# 03cpu_sodimm.net
KiCad netlist of a schematic drawn in Altium Designer
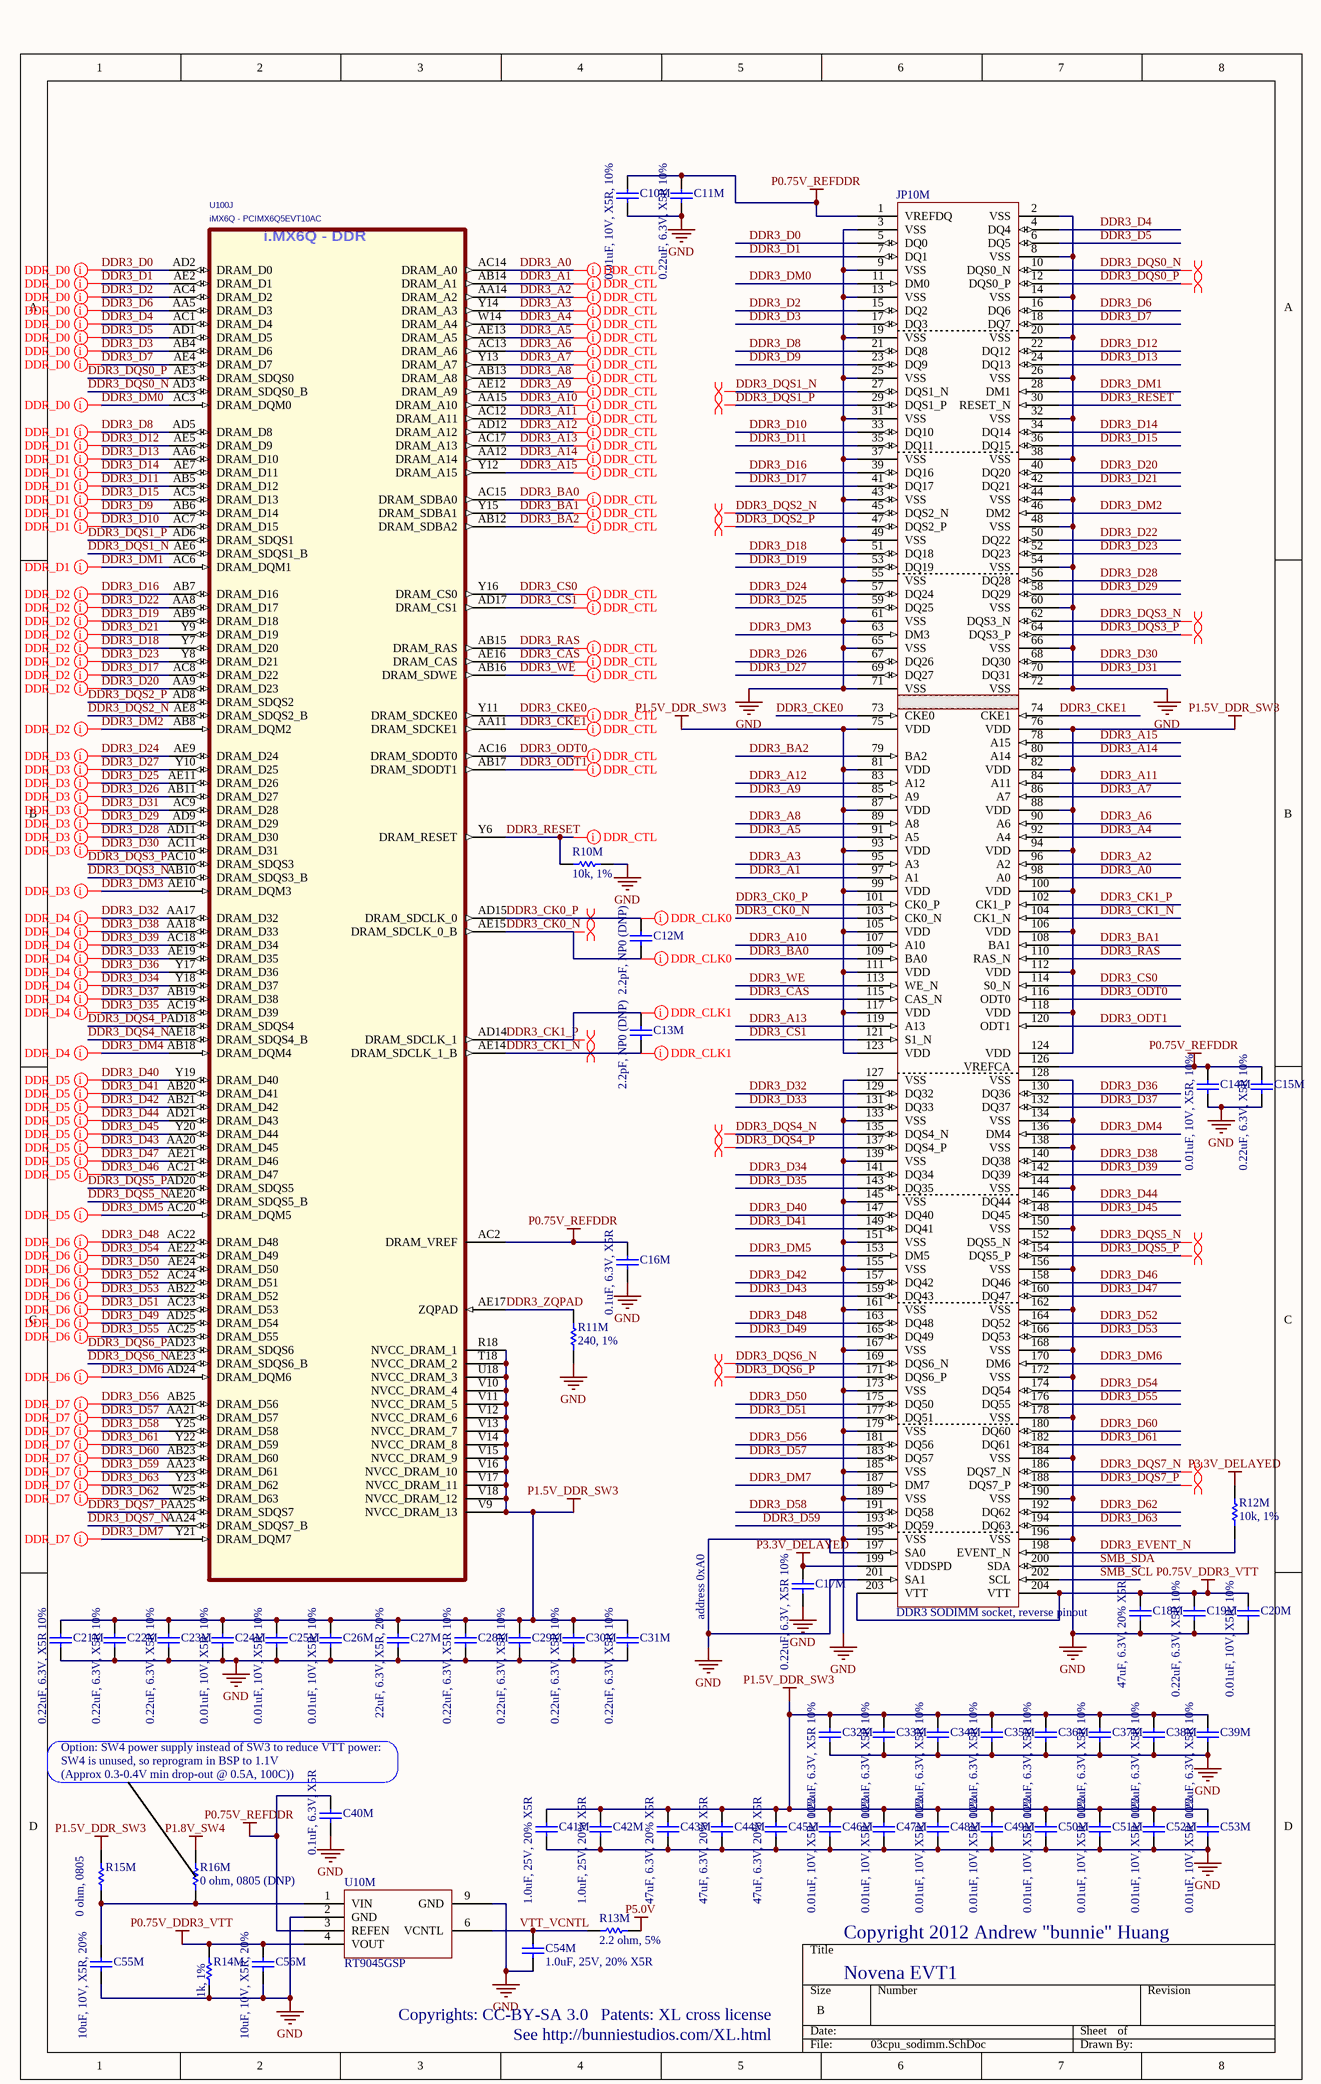
[diagram p0: 03cpu_sodimm.SchDoc]

(export (version "E")
  (design (tool "Eeschema 10.0.6"))
  (components
    (comp (ref "C10M")
      (value "0.01uF, 10V, X5R, 10%")
      (footprint "CAPC0603N_B")
      (description "Capacitor (Semiconductor SIM Model)")
      (fields (field (name "PUBLISHER") "Altium Limited"))
      (libsource (lib "Miscellaneous Devices") (part "Cap Semi"))
    )
    (comp (ref "C11M")
      (value "0.22uF, 6.3V, X5R 10%")
      (footprint "CAPC0603N_B")
      (description "CAP CER 0.22UF 6.3V 20% X5R 0201")
      (fields (field (name "PUBLISHER") "Altium Limited"))
      (libsource (lib "Miscellaneous Devices") (part "Cap Semi"))
    )
    (comp (ref "C12M")
      (value "2.2pF, NP0 (DNP)")
      (footprint "CAPC1005N")
      (description "Capacitor (Semiconductor SIM Model)")
      (fields (field (name "PUBLISHER") "Altium Limited"))
      (libsource (lib "Miscellaneous Devices") (part "Cap Semi"))
    )
    (comp (ref "C13M")
      (value "2.2pF, NP0 (DNP)")
      (footprint "CAPC1005N")
      (description "Capacitor (Semiconductor SIM Model)")
      (fields (field (name "PUBLISHER") "Altium Limited"))
      (libsource (lib "Miscellaneous Devices") (part "Cap Semi"))
    )
    (comp (ref "C14M")
      (value "0.01uF, 10V, X5R, 10%")
      (footprint "CAPC0603N_B")
      (description "Capacitor (Semiconductor SIM Model)")
      (fields (field (name "PUBLISHER") "Altium Limited"))
      (libsource (lib "Miscellaneous Devices") (part "Cap Semi"))
    )
    (comp (ref "C15M")
      (value "0.22uF, 6.3V, X5R 10%")
      (footprint "CAPC0603N_B")
      (description "CAP CER 0.22UF 6.3V 20% X5R 0201")
      (fields (field (name "PUBLISHER") "Altium Limited"))
      (libsource (lib "Miscellaneous Devices") (part "Cap Semi"))
    )
    (comp (ref "C16M")
      (value "0.1uF, 6.3V, X5R")
      (footprint "CAPC0603N_B")
      (description "Capacitor (Semiconductor SIM Model)")
      (fields (field (name "PUBLISHER") "Altium Limited"))
      (libsource (lib "Miscellaneous Devices") (part "Cap Semi"))
    )
    (comp (ref "C17M")
      (value "0.22uF, 6.3V, X5R 10%")
      (footprint "CAPC0603N_B")
      (description "CAP CER 0.22UF 6.3V 20% X5R 0201")
      (fields (field (name "PUBLISHER") "Altium Limited"))
      (libsource (lib "Miscellaneous Devices") (part "Cap Semi"))
    )
    (comp (ref "C18M")
      (value "47uF, 6.3V, 20% X5R")
      (footprint "CAPC3216N")
      (description "Capacitor (Semiconductor SIM Model)")
      (fields (field (name "PUBLISHER") "Altium Limited"))
      (libsource (lib "Miscellaneous Devices") (part "Cap Semi"))
    )
    (comp (ref "C19M")
      (value "0.22uF, 6.3V, X5R 10%")
      (footprint "CAPC0603N_B")
      (description "CAP CER 0.22UF 6.3V 20% X5R 0201")
      (fields (field (name "PUBLISHER") "Altium Limited"))
      (libsource (lib "Miscellaneous Devices") (part "Cap Semi"))
    )
    (comp (ref "C20M")
      (value "0.01uF, 10V, X5R, 10%")
      (footprint "CAPC0603N_B")
      (description "Capacitor (Semiconductor SIM Model)")
      (fields (field (name "PUBLISHER") "Altium Limited"))
      (libsource (lib "Miscellaneous Devices") (part "Cap Semi"))
    )
    (comp (ref "C21M")
      (value "0.22uF, 6.3V, X5R 10%")
      (footprint "CAPC0603N_B")
      (description "CAP CER 0.22UF 6.3V 20% X5R 0201")
      (fields (field (name "PUBLISHER") "Altium Limited"))
      (libsource (lib "Miscellaneous Devices") (part "Cap Semi"))
    )
    (comp (ref "C22M")
      (value "0.22uF, 6.3V, X5R 10%")
      (footprint "CAPC0603N_B")
      (description "CAP CER 0.22UF 6.3V 20% X5R 0201")
      (fields (field (name "PUBLISHER") "Altium Limited"))
      (libsource (lib "Miscellaneous Devices") (part "Cap Semi"))
    )
    (comp (ref "C23M")
      (value "0.22uF, 6.3V, X5R 10%")
      (footprint "CAPC0603N_B")
      (description "CAP CER 0.22UF 6.3V 20% X5R 0201")
      (fields (field (name "PUBLISHER") "Altium Limited"))
      (libsource (lib "Miscellaneous Devices") (part "Cap Semi"))
    )
    (comp (ref "C24M")
      (value "0.01uF, 10V, X5R, 10%")
      (footprint "CAPC0603N_B")
      (description "Capacitor (Semiconductor SIM Model)")
      (fields (field (name "PUBLISHER") "Altium Limited"))
      (libsource (lib "Miscellaneous Devices") (part "Cap Semi"))
    )
    (comp (ref "C25M")
      (value "0.01uF, 10V, X5R, 10%")
      (footprint "CAPC0603N_B")
      (description "Capacitor (Semiconductor SIM Model)")
      (fields (field (name "PUBLISHER") "Altium Limited"))
      (libsource (lib "Miscellaneous Devices") (part "Cap Semi"))
    )
    (comp (ref "C26M")
      (value "0.01uF, 10V, X5R, 10%")
      (footprint "CAPC0603N_B")
      (description "Capacitor (Semiconductor SIM Model)")
      (fields (field (name "PUBLISHER") "Altium Limited"))
      (libsource (lib "Miscellaneous Devices") (part "Cap Semi"))
    )
    (comp (ref "C27M")
      (value "22uF, 6.3V, X5R, 20%")
      (footprint "CAPC1608N_HD")
      (description "Capacitor (Semiconductor SIM Model)")
      (fields (field (name "PUBLISHER") "Altium Limited"))
      (libsource (lib "Miscellaneous Devices") (part "Cap Semi"))
    )
    (comp (ref "C28M")
      (value "0.22uF, 6.3V, X5R 10%")
      (footprint "CAPC0603N_B")
      (description "CAP CER 0.22UF 6.3V 20% X5R 0201")
      (fields (field (name "PUBLISHER") "Altium Limited"))
      (libsource (lib "Miscellaneous Devices") (part "Cap Semi"))
    )
    (comp (ref "C29M")
      (value "0.22uF, 6.3V, X5R 10%")
      (footprint "CAPC0603N_B")
      (description "CAP CER 0.22UF 6.3V 20% X5R 0201")
      (fields (field (name "PUBLISHER") "Altium Limited"))
      (libsource (lib "Miscellaneous Devices") (part "Cap Semi"))
    )
    (comp (ref "C30M")
      (value "0.22uF, 6.3V, X5R 10%")
      (footprint "CAPC0603N_B")
      (description "CAP CER 0.22UF 6.3V 20% X5R 0201")
      (fields (field (name "PUBLISHER") "Altium Limited"))
      (libsource (lib "Miscellaneous Devices") (part "Cap Semi"))
    )
    (comp (ref "C31M")
      (value "0.22uF, 6.3V, X5R 10%")
      (footprint "CAPC0603N_B")
      (description "CAP CER 0.22UF 6.3V 20% X5R 0201")
      (fields (field (name "PUBLISHER") "Altium Limited"))
      (libsource (lib "Miscellaneous Devices") (part "Cap Semi"))
    )
    (comp (ref "C32M")
      (value "0.22uF, 6.3V, X5R 10%")
      (footprint "CAPC0603N_B")
      (description "CAP CER 0.22UF 6.3V 20% X5R 0201")
      (fields (field (name "PUBLISHER") "Altium Limited"))
      (libsource (lib "Miscellaneous Devices") (part "Cap Semi"))
    )
    (comp (ref "C33M")
      (value "0.22uF, 6.3V, X5R 10%")
      (footprint "CAPC0603N_B")
      (description "CAP CER 0.22UF 6.3V 20% X5R 0201")
      (fields (field (name "PUBLISHER") "Altium Limited"))
      (libsource (lib "Miscellaneous Devices") (part "Cap Semi"))
    )
    (comp (ref "C34M")
      (value "0.22uF, 6.3V, X5R 10%")
      (footprint "CAPC0603N_B")
      (description "CAP CER 0.22UF 6.3V 20% X5R 0201")
      (fields (field (name "PUBLISHER") "Altium Limited"))
      (libsource (lib "Miscellaneous Devices") (part "Cap Semi"))
    )
    (comp (ref "C35M")
      (value "0.22uF, 6.3V, X5R 10%")
      (footprint "CAPC0603N_B")
      (description "CAP CER 0.22UF 6.3V 20% X5R 0201")
      (fields (field (name "PUBLISHER") "Altium Limited"))
      (libsource (lib "Miscellaneous Devices") (part "Cap Semi"))
    )
    (comp (ref "C36M")
      (value "0.22uF, 6.3V, X5R 10%")
      (footprint "CAPC0603N_B")
      (description "CAP CER 0.22UF 6.3V 20% X5R 0201")
      (fields (field (name "PUBLISHER") "Altium Limited"))
      (libsource (lib "Miscellaneous Devices") (part "Cap Semi"))
    )
    (comp (ref "C37M")
      (value "0.22uF, 6.3V, X5R 10%")
      (footprint "CAPC0603N_B")
      (description "CAP CER 0.22UF 6.3V 20% X5R 0201")
      (fields (field (name "PUBLISHER") "Altium Limited"))
      (libsource (lib "Miscellaneous Devices") (part "Cap Semi"))
    )
    (comp (ref "C38M")
      (value "0.22uF, 6.3V, X5R 10%")
      (footprint "CAPC0603N_B")
      (description "CAP CER 0.22UF 6.3V 20% X5R 0201")
      (fields (field (name "PUBLISHER") "Altium Limited"))
      (libsource (lib "Miscellaneous Devices") (part "Cap Semi"))
    )
    (comp (ref "C39M")
      (value "0.22uF, 6.3V, X5R 10%")
      (footprint "CAPC0603N_B")
      (description "CAP CER 0.22UF 6.3V 20% X5R 0201")
      (fields (field (name "PUBLISHER") "Altium Limited"))
      (libsource (lib "Miscellaneous Devices") (part "Cap Semi"))
    )
    (comp (ref "C40M")
      (value "0.1uF, 6.3V, X5R")
      (footprint "CAPC0603N_B")
      (description "Capacitor (Semiconductor SIM Model)")
      (fields (field (name "PUBLISHER") "Altium Limited"))
      (libsource (lib "Miscellaneous Devices") (part "Cap Semi"))
    )
    (comp (ref "C41M")
      (value "1.0uF, 25V, 20% X5R")
      (footprint "CAPC1608N")
      (description "Capacitor (Semiconductor SIM Model)")
      (fields (field (name "PUBLISHER") "Altium Limited"))
      (libsource (lib "Miscellaneous Devices") (part "Cap Semi"))
    )
    (comp (ref "C42M")
      (value "1.0uF, 25V, 20% X5R")
      (footprint "CAPC1608N")
      (description "Capacitor (Semiconductor SIM Model)")
      (fields (field (name "PUBLISHER") "Altium Limited"))
      (libsource (lib "Miscellaneous Devices") (part "Cap Semi"))
    )
    (comp (ref "C43M")
      (value "47uF, 6.3V, 20% X5R")
      (footprint "CAPC3216N")
      (description "Capacitor (Semiconductor SIM Model)")
      (fields (field (name "PUBLISHER") "Altium Limited"))
      (libsource (lib "Miscellaneous Devices") (part "Cap Semi"))
    )
    (comp (ref "C44M")
      (value "47uF, 6.3V, 20% X5R")
      (footprint "CAPC3216N")
      (description "Capacitor (Semiconductor SIM Model)")
      (fields (field (name "PUBLISHER") "Altium Limited"))
      (libsource (lib "Miscellaneous Devices") (part "Cap Semi"))
    )
    (comp (ref "C45M")
      (value "47uF, 6.3V, 20% X5R")
      (footprint "CAPC3216N")
      (description "Capacitor (Semiconductor SIM Model)")
      (fields (field (name "PUBLISHER") "Altium Limited"))
      (libsource (lib "Miscellaneous Devices") (part "Cap Semi"))
    )
    (comp (ref "C46M")
      (value "0.01uF, 10V, X5R, 10%")
      (footprint "CAPC0603N_B")
      (description "Capacitor (Semiconductor SIM Model)")
      (fields (field (name "PUBLISHER") "Altium Limited"))
      (libsource (lib "Miscellaneous Devices") (part "Cap Semi"))
    )
    (comp (ref "C47M")
      (value "0.01uF, 10V, X5R, 10%")
      (footprint "CAPC0603N_B")
      (description "Capacitor (Semiconductor SIM Model)")
      (fields (field (name "PUBLISHER") "Altium Limited"))
      (libsource (lib "Miscellaneous Devices") (part "Cap Semi"))
    )
    (comp (ref "C48M")
      (value "0.01uF, 10V, X5R, 10%")
      (footprint "CAPC0603N_B")
      (description "Capacitor (Semiconductor SIM Model)")
      (fields (field (name "PUBLISHER") "Altium Limited"))
      (libsource (lib "Miscellaneous Devices") (part "Cap Semi"))
    )
    (comp (ref "C49M")
      (value "0.01uF, 10V, X5R, 10%")
      (footprint "CAPC0603N_B")
      (description "Capacitor (Semiconductor SIM Model)")
      (fields (field (name "PUBLISHER") "Altium Limited"))
      (libsource (lib "Miscellaneous Devices") (part "Cap Semi"))
    )
    (comp (ref "C50M")
      (value "0.01uF, 10V, X5R, 10%")
      (footprint "CAPC0603N_B")
      (description "Capacitor (Semiconductor SIM Model)")
      (fields (field (name "PUBLISHER") "Altium Limited"))
      (libsource (lib "Miscellaneous Devices") (part "Cap Semi"))
    )
    (comp (ref "C51M")
      (value "0.01uF, 10V, X5R, 10%")
      (footprint "CAPC0603N_B")
      (description "Capacitor (Semiconductor SIM Model)")
      (fields (field (name "PUBLISHER") "Altium Limited"))
      (libsource (lib "Miscellaneous Devices") (part "Cap Semi"))
    )
    (comp (ref "C52M")
      (value "0.01uF, 10V, X5R, 10%")
      (footprint "CAPC0603N_B")
      (description "Capacitor (Semiconductor SIM Model)")
      (fields (field (name "PUBLISHER") "Altium Limited"))
      (libsource (lib "Miscellaneous Devices") (part "Cap Semi"))
    )
    (comp (ref "C53M")
      (value "0.01uF, 10V, X5R, 10%")
      (footprint "CAPC0603N_B")
      (description "Capacitor (Semiconductor SIM Model)")
      (fields (field (name "PUBLISHER") "Altium Limited"))
      (libsource (lib "Miscellaneous Devices") (part "Cap Semi"))
    )
    (comp (ref "C54M")
      (value "1.0uF, 25V, 20% X5R")
      (footprint "CAPC1608N")
      (description "Capacitor (Semiconductor SIM Model)")
      (fields (field (name "PUBLISHER") "Altium Limited"))
      (libsource (lib "Miscellaneous Devices") (part "Cap Semi"))
    )
    (comp (ref "C55M")
      (value "10uF, 10V, X5R, 20%")
      (footprint "CAPC1608N")
      (description "Capacitor (Semiconductor SIM Model)")
      (fields (field (name "PUBLISHER") "Altium Limited"))
      (libsource (lib "Miscellaneous Devices") (part "Cap Semi"))
    )
    (comp (ref "C56M")
      (value "10uF, 10V, X5R, 20%")
      (footprint "CAPC1608N")
      (description "Capacitor (Semiconductor SIM Model)")
      (fields (field (name "PUBLISHER") "Altium Limited"))
      (libsource (lib "Miscellaneous Devices") (part "Cap Semi"))
    )
    (comp (ref "JP10M")
      (value "DDR3 SODIMM socket, reverse pinout")
      (footprint "DDR3_SODIMM_REV")
      (description "TE Connectivity 2013311 or equiv (9.2mm height)")
      (libsource (lib "commonsch") (part "DDR3_SODIMM"))
    )
    (comp (ref "R10M")
      (value "10k, 1%")
      (footprint "RESC1005N")
      (description "Resistor")
      (fields (field (name "PUBLISHER") "Altium Limited"))
      (libsource (lib "Miscellaneous Devices") (part "Res1"))
    )
    (comp (ref "R11M")
      (value "240, 1%")
      (footprint "RESC1005N")
      (description "Resistor")
      (fields (field (name "PUBLISHER") "Altium Limited"))
      (libsource (lib "Miscellaneous Devices") (part "Res1"))
    )
    (comp (ref "R12M")
      (value "10k, 1%")
      (footprint "RESC1005N")
      (description "Resistor")
      (fields (field (name "PUBLISHER") "Altium Limited"))
      (libsource (lib "Miscellaneous Devices") (part "Res1"))
    )
    (comp (ref "R13M")
      (value "2.2 ohm, 5%")
      (footprint "RESC1005N")
      (description "Resistor")
      (fields (field (name "PUBLISHER") "Altium Limited"))
      (libsource (lib "Miscellaneous Devices") (part "Res1"))
    )
    (comp (ref "R14M")
      (value "1k, 1%")
      (footprint "RESC1005N")
      (description "Resistor")
      (fields (field (name "PUBLISHER") "Altium Limited"))
      (libsource (lib "Miscellaneous Devices") (part "Res1"))
    )
    (comp (ref "R15M")
      (value "0 ohm, 0805")
      (footprint "RESC2012N")
      (description "Resistor")
      (fields (field (name "PUBLISHER") "Altium Limited"))
      (libsource (lib "Miscellaneous Devices") (part "Res1"))
    )
    (comp (ref "R16M")
      (value "0 ohm, 0805 (DNP)")
      (footprint "RESC2012N")
      (description "Resistor")
      (fields (field (name "PUBLISHER") "Altium Limited"))
      (libsource (lib "Miscellaneous Devices") (part "Res1"))
    )
    (comp (ref "U10M")
      (value "RT9045GSP")
      (footprint "SOIC127P600_HS-8N")
      (description "1.8A sink/source bus termination regulator (VTT)")
      (libsource (lib "commonsch") (part "RT9045GSP"))
    )
    (comp (ref "U100")
      (value "iMX6Q - PCIMX6Q5EVT10AC")
      (description "PLACEHOLDER FOR FREESCALE PART NUMBER PMCIMX6Q6VV1A.")
      (libsource (lib "*") (part "PCIMX6Q6VV1A"))
    )
  )
  (nets
    (net (code "1") (name "/DDR3_A0") (class "Default")
      (node (ref "JP10M") (pin "98") (pinfunction "A0_98") (pintype "input"))
      (node (ref "U100") (pin "AC14") (pinfunction "DRAM_A0_AC14") (pintype "output"))
    )
    (net (code "2") (name "/DDR3_A1") (class "Default")
      (node (ref "JP10M") (pin "97") (pinfunction "A1_97") (pintype "input"))
      (node (ref "U100") (pin "AB14") (pinfunction "DRAM_A1_AB14") (pintype "output"))
    )
    (net (code "3") (name "/DDR3_A2") (class "Default")
      (node (ref "JP10M") (pin "96") (pinfunction "A2_96") (pintype "input"))
      (node (ref "U100") (pin "AA14") (pinfunction "DRAM_A2_AA14") (pintype "output"))
    )
    (net (code "4") (name "/DDR3_A3") (class "Default")
      (node (ref "JP10M") (pin "95") (pinfunction "A3_95") (pintype "input"))
      (node (ref "U100") (pin "Y14") (pinfunction "DRAM_A3_Y14") (pintype "output"))
    )
    (net (code "5") (name "/DDR3_A4") (class "Default")
      (node (ref "JP10M") (pin "92") (pinfunction "A4_92") (pintype "input"))
      (node (ref "U100") (pin "W14") (pinfunction "DRAM_A4_W14") (pintype "output"))
    )
    (net (code "6") (name "/DDR3_A5") (class "Default")
      (node (ref "JP10M") (pin "91") (pinfunction "A5_91") (pintype "input"))
      (node (ref "U100") (pin "AE13") (pinfunction "DRAM_A5_AE13") (pintype "output"))
    )
    (net (code "7") (name "/DDR3_A6") (class "Default")
      (node (ref "JP10M") (pin "90") (pinfunction "A6_90") (pintype "input"))
      (node (ref "U100") (pin "AC13") (pinfunction "DRAM_A6_AC13") (pintype "output"))
    )
    (net (code "8") (name "/DDR3_A7") (class "Default")
      (node (ref "JP10M") (pin "86") (pinfunction "A7_86") (pintype "input"))
      (node (ref "U100") (pin "Y13") (pinfunction "DRAM_A7_Y13") (pintype "output"))
    )
    (net (code "9") (name "/DDR3_A8") (class "Default")
      (node (ref "JP10M") (pin "89") (pinfunction "A8_89") (pintype "input"))
      (node (ref "U100") (pin "AB13") (pinfunction "DRAM_A8_AB13") (pintype "output"))
    )
    (net (code "10") (name "/DDR3_A9") (class "Default")
      (node (ref "JP10M") (pin "85") (pinfunction "A9_85") (pintype "input"))
      (node (ref "U100") (pin "AE12") (pinfunction "DRAM_A9_AE12") (pintype "output"))
    )
    (net (code "11") (name "/DDR3_A10") (class "Default")
      (node (ref "JP10M") (pin "107") (pinfunction "A10_107") (pintype "input"))
      (node (ref "U100") (pin "AA15") (pinfunction "DRAM_A10_AA15") (pintype "output"))
    )
    (net (code "12") (name "/DDR3_A11") (class "Default")
      (node (ref "JP10M") (pin "84") (pinfunction "A11_84") (pintype "input"))
      (node (ref "U100") (pin "AC12") (pinfunction "DRAM_A11_AC12") (pintype "output"))
    )
    (net (code "13") (name "/DDR3_A12") (class "Default")
      (node (ref "JP10M") (pin "83") (pinfunction "A12_83") (pintype "input"))
      (node (ref "U100") (pin "AD12") (pinfunction "DRAM_A12_AD12") (pintype "output"))
    )
    (net (code "14") (name "/DDR3_A13") (class "Default")
      (node (ref "JP10M") (pin "119") (pinfunction "A13_119") (pintype "input"))
      (node (ref "U100") (pin "AC17") (pinfunction "DRAM_A13_AC17") (pintype "output"))
    )
    (net (code "15") (name "/DDR3_A14") (class "Default")
      (node (ref "JP10M") (pin "80") (pinfunction "A14_80") (pintype "input"))
      (node (ref "U100") (pin "AA12") (pinfunction "DRAM_A14_AA12") (pintype "output"))
    )
    (net (code "16") (name "/DDR3_A15") (class "Default")
      (node (ref "JP10M") (pin "78") (pinfunction "A15_78") (pintype "input"))
      (node (ref "U100") (pin "Y12") (pinfunction "DRAM_A15_Y12") (pintype "output"))
    )
    (net (code "17") (name "/DDR3_BA0") (class "Default")
      (node (ref "JP10M") (pin "109") (pinfunction "BA0_109") (pintype "input"))
      (node (ref "U100") (pin "AC15") (pinfunction "DRAM_SDBA0_AC15") (pintype "output"))
    )
    (net (code "18") (name "/DDR3_BA1") (class "Default")
      (node (ref "JP10M") (pin "108") (pinfunction "BA1_108") (pintype "input"))
      (node (ref "U100") (pin "Y15") (pinfunction "DRAM_SDBA1_Y15") (pintype "output"))
    )
    (net (code "19") (name "/DDR3_BA2") (class "Default")
      (node (ref "JP10M") (pin "79") (pinfunction "BA2_79") (pintype "input"))
      (node (ref "U100") (pin "AB12") (pinfunction "DRAM_SDBA2_AB12") (pintype "output"))
    )
    (net (code "20") (name "/DDR3_CAS") (class "Default")
      (node (ref "JP10M") (pin "115") (pinfunction "CAS_N_115") (pintype "input"))
      (node (ref "U100") (pin "AE16") (pinfunction "DRAM_CAS_AE16") (pintype "output"))
    )
    (net (code "21") (name "/DDR3_CK0_N") (class "Default")
      (node (ref "C12M") (pin "2") (pinfunction "2_2") (pintype "passive"))
      (node (ref "JP10M") (pin "103") (pinfunction "CK0_N_103") (pintype "input"))
      (node (ref "U100") (pin "AE15") (pinfunction "DRAM_SDCLK_0_B_AE15") (pintype "output"))
    )
    (net (code "22") (name "/DDR3_CK0_P") (class "Default")
      (node (ref "C12M") (pin "1") (pinfunction "1_1") (pintype "passive"))
      (node (ref "JP10M") (pin "101") (pinfunction "CK0_P_101") (pintype "input"))
      (node (ref "U100") (pin "AD15") (pinfunction "DRAM_SDCLK_0_AD15") (pintype "output"))
    )
    (net (code "23") (name "/DDR3_CK1_N") (class "Default")
      (node (ref "C13M") (pin "2") (pinfunction "2_2") (pintype "passive"))
      (node (ref "JP10M") (pin "104") (pinfunction "CK1_N_104") (pintype "input"))
      (node (ref "U100") (pin "AE14") (pinfunction "DRAM_SDCLK_1_B_AE14") (pintype "output"))
    )
    (net (code "24") (name "/DDR3_CK1_P") (class "Default")
      (node (ref "C13M") (pin "1") (pinfunction "1_1") (pintype "passive"))
      (node (ref "JP10M") (pin "102") (pinfunction "CK1_P_102") (pintype "input"))
      (node (ref "U100") (pin "AD14") (pinfunction "DRAM_SDCLK_1_AD14") (pintype "output"))
    )
    (net (code "25") (name "/DDR3_CKE0") (class "Default")
      (node (ref "JP10M") (pin "73") (pinfunction "CKE0_73") (pintype "input"))
      (node (ref "U100") (pin "Y11") (pinfunction "DRAM_SDCKE0_Y11") (pintype "output"))
    )
    (net (code "26") (name "/DDR3_CKE1") (class "Default")
      (node (ref "JP10M") (pin "74") (pinfunction "CKE1_74") (pintype "input"))
      (node (ref "U100") (pin "AA11") (pinfunction "DRAM_SDCKE1_AA11") (pintype "output"))
    )
    (net (code "27") (name "/DDR3_CS0") (class "Default")
      (node (ref "JP10M") (pin "114") (pinfunction "S0_N_114") (pintype "input"))
      (node (ref "U100") (pin "Y16") (pinfunction "DRAM_CS0_Y16") (pintype "output"))
    )
    (net (code "28") (name "/DDR3_CS1") (class "Default")
      (node (ref "JP10M") (pin "121") (pinfunction "S1_N_121") (pintype "input"))
      (node (ref "U100") (pin "AD17") (pinfunction "DRAM_CS1_AD17") (pintype "output"))
    )
    (net (code "29") (name "/DDR3_D0") (class "Default")
      (node (ref "JP10M") (pin "5") (pinfunction "DQ0_5") (pintype "bidirectional"))
      (node (ref "U100") (pin "AD2") (pinfunction "DRAM_D0_AD2") (pintype "bidirectional"))
    )
    (net (code "30") (name "/DDR3_D1") (class "Default")
      (node (ref "JP10M") (pin "7") (pinfunction "DQ1_7") (pintype "bidirectional"))
      (node (ref "U100") (pin "AE2") (pinfunction "DRAM_D1_AE2") (pintype "bidirectional"))
    )
    (net (code "31") (name "/DDR3_D2") (class "Default")
      (node (ref "JP10M") (pin "15") (pinfunction "DQ2_15") (pintype "bidirectional"))
      (node (ref "U100") (pin "AC4") (pinfunction "DRAM_D2_AC4") (pintype "bidirectional"))
    )
    (net (code "32") (name "/DDR3_D3") (class "Default")
      (node (ref "JP10M") (pin "17") (pinfunction "DQ3_17") (pintype "bidirectional"))
      (node (ref "U100") (pin "AB4") (pinfunction "DRAM_D6_AB4") (pintype "bidirectional"))
    )
    (net (code "33") (name "/DDR3_D4") (class "Default")
      (node (ref "JP10M") (pin "4") (pinfunction "DQ4_4") (pintype "bidirectional"))
      (node (ref "U100") (pin "AC1") (pinfunction "DRAM_D4_AC1") (pintype "bidirectional"))
    )
    (net (code "34") (name "/DDR3_D5") (class "Default")
      (node (ref "JP10M") (pin "6") (pinfunction "DQ5_6") (pintype "bidirectional"))
      (node (ref "U100") (pin "AD1") (pinfunction "DRAM_D5_AD1") (pintype "bidirectional"))
    )
    (net (code "35") (name "/DDR3_D6") (class "Default")
      (node (ref "JP10M") (pin "16") (pinfunction "DQ6_16") (pintype "bidirectional"))
      (node (ref "U100") (pin "AA5") (pinfunction "DRAM_D3_AA5") (pintype "bidirectional"))
    )
    (net (code "36") (name "/DDR3_D7") (class "Default")
      (node (ref "JP10M") (pin "18") (pinfunction "DQ7_18") (pintype "bidirectional"))
      (node (ref "U100") (pin "AE4") (pinfunction "DRAM_D7_AE4") (pintype "bidirectional"))
    )
    (net (code "37") (name "/DDR3_D8") (class "Default")
      (node (ref "JP10M") (pin "21") (pinfunction "DQ8_21") (pintype "bidirectional"))
      (node (ref "U100") (pin "AD5") (pinfunction "DRAM_D8_AD5") (pintype "bidirectional"))
    )
    (net (code "38") (name "/DDR3_D9") (class "Default")
      (node (ref "JP10M") (pin "23") (pinfunction "DQ9_23") (pintype "bidirectional"))
      (node (ref "U100") (pin "AB6") (pinfunction "DRAM_D14_AB6") (pintype "bidirectional"))
    )
    (net (code "39") (name "/DDR3_D10") (class "Default")
      (node (ref "JP10M") (pin "33") (pinfunction "DQ10_33") (pintype "bidirectional"))
      (node (ref "U100") (pin "AC7") (pinfunction "DRAM_D15_AC7") (pintype "bidirectional"))
    )
    (net (code "40") (name "/DDR3_D11") (class "Default")
      (node (ref "JP10M") (pin "35") (pinfunction "DQ11_35") (pintype "bidirectional"))
      (node (ref "U100") (pin "AB5") (pinfunction "DRAM_D12_AB5") (pintype "bidirectional"))
    )
    (net (code "41") (name "/DDR3_D12") (class "Default")
      (node (ref "JP10M") (pin "22") (pinfunction "DQ12_22") (pintype "bidirectional"))
      (node (ref "U100") (pin "AE5") (pinfunction "DRAM_D9_AE5") (pintype "bidirectional"))
    )
    (net (code "42") (name "/DDR3_D13") (class "Default")
      (node (ref "JP10M") (pin "24") (pinfunction "DQ13_24") (pintype "bidirectional"))
      (node (ref "U100") (pin "AA6") (pinfunction "DRAM_D10_AA6") (pintype "bidirectional"))
    )
    (net (code "43") (name "/DDR3_D14") (class "Default")
      (node (ref "JP10M") (pin "34") (pinfunction "DQ14_34") (pintype "bidirectional"))
      (node (ref "U100") (pin "AE7") (pinfunction "DRAM_D11_AE7") (pintype "bidirectional"))
    )
    (net (code "44") (name "/DDR3_D15") (class "Default")
      (node (ref "JP10M") (pin "36") (pinfunction "DQ15_36") (pintype "bidirectional"))
      (node (ref "U100") (pin "AC5") (pinfunction "DRAM_D13_AC5") (pintype "bidirectional"))
    )
    (net (code "45") (name "/DDR3_D16") (class "Default")
      (node (ref "JP10M") (pin "39") (pinfunction "DQ16_39") (pintype "bidirectional"))
      (node (ref "U100") (pin "AB7") (pinfunction "DRAM_D16_AB7") (pintype "bidirectional"))
    )
    (net (code "46") (name "/DDR3_D17") (class "Default")
      (node (ref "JP10M") (pin "41") (pinfunction "DQ17_41") (pintype "bidirectional"))
      (node (ref "U100") (pin "AC8") (pinfunction "DRAM_D22_AC8") (pintype "bidirectional"))
    )
    (net (code "47") (name "/DDR3_D18") (class "Default")
      (node (ref "JP10M") (pin "51") (pinfunction "DQ18_51") (pintype "bidirectional"))
      (node (ref "U100") (pin "Y7") (pinfunction "DRAM_D20_Y7") (pintype "bidirectional"))
    )
    (net (code "48") (name "/DDR3_D19") (class "Default")
      (node (ref "JP10M") (pin "53") (pinfunction "DQ19_53") (pintype "bidirectional"))
      (node (ref "U100") (pin "AB9") (pinfunction "DRAM_D18_AB9") (pintype "bidirectional"))
    )
    (net (code "49") (name "/DDR3_D20") (class "Default")
      (node (ref "JP10M") (pin "40") (pinfunction "DQ20_40") (pintype "bidirectional"))
      (node (ref "U100") (pin "AA9") (pinfunction "DRAM_D23_AA9") (pintype "bidirectional"))
    )
    (net (code "50") (name "/DDR3_D21") (class "Default")
      (node (ref "JP10M") (pin "42") (pinfunction "DQ21_42") (pintype "bidirectional"))
      (node (ref "U100") (pin "Y9") (pinfunction "DRAM_D19_Y9") (pintype "bidirectional"))
    )
    (net (code "51") (name "/DDR3_D22") (class "Default")
      (node (ref "JP10M") (pin "50") (pinfunction "DQ22_50") (pintype "bidirectional"))
      (node (ref "U100") (pin "AA8") (pinfunction "DRAM_D17_AA8") (pintype "bidirectional"))
    )
    (net (code "52") (name "/DDR3_D23") (class "Default")
      (node (ref "JP10M") (pin "52") (pinfunction "DQ23_52") (pintype "bidirectional"))
      (node (ref "U100") (pin "Y8") (pinfunction "DRAM_D21_Y8") (pintype "bidirectional"))
    )
    (net (code "53") (name "/DDR3_D24") (class "Default")
      (node (ref "JP10M") (pin "57") (pinfunction "DQ24_57") (pintype "bidirectional"))
      (node (ref "U100") (pin "AE9") (pinfunction "DRAM_D24_AE9") (pintype "bidirectional"))
    )
    (net (code "54") (name "/DDR3_D25") (class "Default")
      (node (ref "JP10M") (pin "59") (pinfunction "DQ25_59") (pintype "bidirectional"))
      (node (ref "U100") (pin "AE11") (pinfunction "DRAM_D26_AE11") (pintype "bidirectional"))
    )
    (net (code "55") (name "/DDR3_D26") (class "Default")
      (node (ref "JP10M") (pin "67") (pinfunction "DQ26_67") (pintype "bidirectional"))
      (node (ref "U100") (pin "AB11") (pinfunction "DRAM_D27_AB11") (pintype "bidirectional"))
    )
    (net (code "56") (name "/DDR3_D27") (class "Default")
      (node (ref "JP10M") (pin "69") (pinfunction "DQ27_69") (pintype "bidirectional"))
      (node (ref "U100") (pin "Y10") (pinfunction "DRAM_D25_Y10") (pintype "bidirectional"))
    )
    (net (code "57") (name "/DDR3_D28") (class "Default")
      (node (ref "JP10M") (pin "56") (pinfunction "DQ28_56") (pintype "bidirectional"))
      (node (ref "U100") (pin "AD11") (pinfunction "DRAM_D30_AD11") (pintype "bidirectional"))
    )
    (net (code "58") (name "/DDR3_D29") (class "Default")
      (node (ref "JP10M") (pin "58") (pinfunction "DQ29_58") (pintype "bidirectional"))
      (node (ref "U100") (pin "AD9") (pinfunction "DRAM_D29_AD9") (pintype "bidirectional"))
    )
    (net (code "59") (name "/DDR3_D30") (class "Default")
      (node (ref "JP10M") (pin "68") (pinfunction "DQ30_68") (pintype "bidirectional"))
      (node (ref "U100") (pin "AC11") (pinfunction "DRAM_D31_AC11") (pintype "bidirectional"))
    )
    (net (code "60") (name "/DDR3_D31") (class "Default")
      (node (ref "JP10M") (pin "70") (pinfunction "DQ31_70") (pintype "bidirectional"))
      (node (ref "U100") (pin "AC9") (pinfunction "DRAM_D28_AC9") (pintype "bidirectional"))
    )
    (net (code "61") (name "/DDR3_D32") (class "Default")
      (node (ref "JP10M") (pin "129") (pinfunction "DQ32_129") (pintype "bidirectional"))
      (node (ref "U100") (pin "AA17") (pinfunction "DRAM_D32_AA17") (pintype "bidirectional"))
    )
    (net (code "62") (name "/DDR3_D33") (class "Default")
      (node (ref "JP10M") (pin "131") (pinfunction "DQ33_131") (pintype "bidirectional"))
      (node (ref "U100") (pin "AE19") (pinfunction "DRAM_D35_AE19") (pintype "bidirectional"))
    )
    (net (code "63") (name "/DDR3_D34") (class "Default")
      (node (ref "JP10M") (pin "141") (pinfunction "DQ34_141") (pintype "bidirectional"))
      (node (ref "U100") (pin "Y18") (pinfunction "DRAM_D37_Y18") (pintype "bidirectional"))
    )
    (net (code "64") (name "/DDR3_D35") (class "Default")
      (node (ref "JP10M") (pin "143") (pinfunction "DQ35_143") (pintype "bidirectional"))
      (node (ref "U100") (pin "AC19") (pinfunction "DRAM_D39_AC19") (pintype "bidirectional"))
    )
    (net (code "65") (name "/DDR3_D36") (class "Default")
      (node (ref "JP10M") (pin "130") (pinfunction "DQ36_130") (pintype "bidirectional"))
      (node (ref "U100") (pin "Y17") (pinfunction "DRAM_D36_Y17") (pintype "bidirectional"))
    )
    (net (code "66") (name "/DDR3_D37") (class "Default")
      (node (ref "JP10M") (pin "132") (pinfunction "DQ37_132") (pintype "bidirectional"))
      (node (ref "U100") (pin "AB19") (pinfunction "DRAM_D38_AB19") (pintype "bidirectional"))
    )
    (net (code "67") (name "/DDR3_D38") (class "Default")
      (node (ref "JP10M") (pin "140") (pinfunction "DQ38_140") (pintype "bidirectional"))
      (node (ref "U100") (pin "AA18") (pinfunction "DRAM_D33_AA18") (pintype "bidirectional"))
    )
    (net (code "68") (name "/DDR3_D39") (class "Default")
      (node (ref "JP10M") (pin "142") (pinfunction "DQ39_142") (pintype "bidirectional"))
      (node (ref "U100") (pin "AC18") (pinfunction "DRAM_D34_AC18") (pintype "bidirectional"))
    )
    (net (code "69") (name "/DDR3_D40") (class "Default")
      (node (ref "JP10M") (pin "147") (pinfunction "DQ40_147") (pintype "bidirectional"))
      (node (ref "U100") (pin "Y19") (pinfunction "DRAM_D40_Y19") (pintype "bidirectional"))
    )
    (net (code "70") (name "/DDR3_D41") (class "Default")
      (node (ref "JP10M") (pin "149") (pinfunction "DQ41_149") (pintype "bidirectional"))
      (node (ref "U100") (pin "AB20") (pinfunction "DRAM_D41_AB20") (pintype "bidirectional"))
    )
    (net (code "71") (name "/DDR3_D42") (class "Default")
      (node (ref "JP10M") (pin "157") (pinfunction "DQ42_157") (pintype "bidirectional"))
      (node (ref "U100") (pin "AB21") (pinfunction "DRAM_D42_AB21") (pintype "bidirectional"))
    )
    (net (code "72") (name "/DDR3_D43") (class "Default")
      (node (ref "JP10M") (pin "159") (pinfunction "DQ43_159") (pintype "bidirectional"))
      (node (ref "U100") (pin "AA20") (pinfunction "DRAM_D45_AA20") (pintype "bidirectional"))
    )
    (net (code "73") (name "/DDR3_D44") (class "Default")
      (node (ref "JP10M") (pin "146") (pinfunction "DQ44_146") (pintype "bidirectional"))
      (node (ref "U100") (pin "AD21") (pinfunction "DRAM_D43_AD21") (pintype "bidirectional"))
    )
    (net (code "74") (name "/DDR3_D45") (class "Default")
      (node (ref "JP10M") (pin "148") (pinfunction "DQ45_148") (pintype "bidirectional"))
      (node (ref "U100") (pin "Y20") (pinfunction "DRAM_D44_Y20") (pintype "bidirectional"))
    )
    (net (code "75") (name "/DDR3_D46") (class "Default")
      (node (ref "JP10M") (pin "158") (pinfunction "DQ46_158") (pintype "bidirectional"))
      (node (ref "U100") (pin "AC21") (pinfunction "DRAM_D47_AC21") (pintype "bidirectional"))
    )
    (net (code "76") (name "/DDR3_D47") (class "Default")
      (node (ref "JP10M") (pin "160") (pinfunction "DQ47_160") (pintype "bidirectional"))
      (node (ref "U100") (pin "AE21") (pinfunction "DRAM_D46_AE21") (pintype "bidirectional"))
    )
    (net (code "77") (name "/DDR3_D48") (class "Default")
      (node (ref "JP10M") (pin "163") (pinfunction "DQ48_163") (pintype "bidirectional"))
      (node (ref "U100") (pin "AC22") (pinfunction "DRAM_D48_AC22") (pintype "bidirectional"))
    )
    (net (code "78") (name "/DDR3_D49") (class "Default")
      (node (ref "JP10M") (pin "165") (pinfunction "DQ49_165") (pintype "bidirectional"))
      (node (ref "U100") (pin "AD25") (pinfunction "DRAM_D54_AD25") (pintype "bidirectional"))
    )
    (net (code "79") (name "/DDR3_D50") (class "Default")
      (node (ref "JP10M") (pin "175") (pinfunction "DQ50_175") (pintype "bidirectional"))
      (node (ref "U100") (pin "AE24") (pinfunction "DRAM_D50_AE24") (pintype "bidirectional"))
    )
    (net (code "80") (name "/DDR3_D51") (class "Default")
      (node (ref "JP10M") (pin "177") (pinfunction "DQ51_177") (pintype "bidirectional"))
      (node (ref "U100") (pin "AC23") (pinfunction "DRAM_D53_AC23") (pintype "bidirectional"))
    )
    (net (code "81") (name "/DDR3_D52") (class "Default")
      (node (ref "JP10M") (pin "164") (pinfunction "DQ52_164") (pintype "bidirectional"))
      (node (ref "U100") (pin "AC24") (pinfunction "DRAM_D51_AC24") (pintype "bidirectional"))
    )
    (net (code "82") (name "/DDR3_D53") (class "Default")
      (node (ref "JP10M") (pin "166") (pinfunction "DQ53_166") (pintype "bidirectional"))
      (node (ref "U100") (pin "AB22") (pinfunction "DRAM_D52_AB22") (pintype "bidirectional"))
    )
    (net (code "83") (name "/DDR3_D54") (class "Default")
      (node (ref "JP10M") (pin "174") (pinfunction "DQ54_174") (pintype "bidirectional"))
      (node (ref "U100") (pin "AE22") (pinfunction "DRAM_D49_AE22") (pintype "bidirectional"))
    )
    (net (code "84") (name "/DDR3_D55") (class "Default")
      (node (ref "JP10M") (pin "176") (pinfunction "DQ55_176") (pintype "bidirectional"))
      (node (ref "U100") (pin "AC25") (pinfunction "DRAM_D55_AC25") (pintype "bidirectional"))
    )
    (net (code "85") (name "/DDR3_D56") (class "Default")
      (node (ref "JP10M") (pin "181") (pinfunction "DQ56_181") (pintype "bidirectional"))
      (node (ref "U100") (pin "AB25") (pinfunction "DRAM_D56_AB25") (pintype "bidirectional"))
    )
    (net (code "86") (name "/DDR3_D57") (class "Default")
      (node (ref "JP10M") (pin "183") (pinfunction "DQ57_183") (pintype "bidirectional"))
      (node (ref "U100") (pin "AA21") (pinfunction "DRAM_D57_AA21") (pintype "bidirectional"))
    )
    (net (code "87") (name "/DDR3_D58") (class "Default")
      (node (ref "JP10M") (pin "191") (pinfunction "DQ58_191") (pintype "bidirectional"))
      (node (ref "U100") (pin "Y25") (pinfunction "DRAM_D58_Y25") (pintype "bidirectional"))
    )
    (net (code "88") (name "/DDR3_D59") (class "Default")
      (node (ref "JP10M") (pin "193") (pinfunction "DQ59_193") (pintype "bidirectional"))
      (node (ref "U100") (pin "AA23") (pinfunction "DRAM_D61_AA23") (pintype "bidirectional"))
    )
    (net (code "89") (name "/DDR3_D60") (class "Default")
      (node (ref "JP10M") (pin "180") (pinfunction "DQ60_180") (pintype "bidirectional"))
      (node (ref "U100") (pin "AB23") (pinfunction "DRAM_D60_AB23") (pintype "bidirectional"))
    )
    (net (code "90") (name "/DDR3_D61") (class "Default")
      (node (ref "JP10M") (pin "182") (pinfunction "DQ61_182") (pintype "bidirectional"))
      (node (ref "U100") (pin "Y22") (pinfunction "DRAM_D59_Y22") (pintype "bidirectional"))
    )
    (net (code "91") (name "/DDR3_D62") (class "Default")
      (node (ref "JP10M") (pin "192") (pinfunction "DQ62_192") (pintype "bidirectional"))
      (node (ref "U100") (pin "W25") (pinfunction "DRAM_D63_W25") (pintype "bidirectional"))
    )
    (net (code "92") (name "/DDR3_D63") (class "Default")
      (node (ref "JP10M") (pin "194") (pinfunction "DQ63_194") (pintype "bidirectional"))
      (node (ref "U100") (pin "Y23") (pinfunction "DRAM_D62_Y23") (pintype "bidirectional"))
    )
    (net (code "93") (name "/DDR3_DM0") (class "Default")
      (node (ref "JP10M") (pin "11") (pinfunction "DM0_11") (pintype "input"))
      (node (ref "U100") (pin "AC3") (pinfunction "DRAM_DQM0_AC3") (pintype "input"))
    )
    (net (code "94") (name "/DDR3_DM1") (class "Default")
      (node (ref "JP10M") (pin "28") (pinfunction "DM1_28") (pintype "input"))
      (node (ref "U100") (pin "AC6") (pinfunction "DRAM_DQM1_AC6") (pintype "input"))
    )
    (net (code "95") (name "/DDR3_DM2") (class "Default")
      (node (ref "JP10M") (pin "46") (pinfunction "DM2_46") (pintype "input"))
      (node (ref "U100") (pin "AB8") (pinfunction "DRAM_DQM2_AB8") (pintype "input"))
    )
    (net (code "96") (name "/DDR3_DM3") (class "Default")
      (node (ref "JP10M") (pin "63") (pinfunction "DM3_63") (pintype "input"))
      (node (ref "U100") (pin "AE10") (pinfunction "DRAM_DQM3_AE10") (pintype "input"))
    )
    (net (code "97") (name "/DDR3_DM4") (class "Default")
      (node (ref "JP10M") (pin "136") (pinfunction "DM4_136") (pintype "input"))
      (node (ref "U100") (pin "AB18") (pinfunction "DRAM_DQM4_AB18") (pintype "input"))
    )
    (net (code "98") (name "/DDR3_DM5") (class "Default")
      (node (ref "JP10M") (pin "153") (pinfunction "DM5_153") (pintype "input"))
      (node (ref "U100") (pin "AC20") (pinfunction "DRAM_DQM5_AC20") (pintype "input"))
    )
    (net (code "99") (name "/DDR3_DM6") (class "Default")
      (node (ref "JP10M") (pin "170") (pinfunction "DM6_170") (pintype "input"))
      (node (ref "U100") (pin "AD24") (pinfunction "DRAM_DQM6_AD24") (pintype "input"))
    )
    (net (code "100") (name "/DDR3_DM7") (class "Default")
      (node (ref "JP10M") (pin "187") (pinfunction "DM7_187") (pintype "input"))
      (node (ref "U100") (pin "Y21") (pinfunction "DRAM_DQM7_Y21") (pintype "input"))
    )
    (net (code "101") (name "/DDR3_DQS0_N") (class "Default")
      (node (ref "JP10M") (pin "10") (pinfunction "DQS0_N_10") (pintype "bidirectional"))
      (node (ref "U100") (pin "AD3") (pinfunction "DRAM_SDQS0_B_AD3") (pintype "bidirectional"))
    )
    (net (code "102") (name "/DDR3_DQS0_P") (class "Default")
      (node (ref "JP10M") (pin "12") (pinfunction "DQS0_P_12") (pintype "bidirectional"))
      (node (ref "U100") (pin "AE3") (pinfunction "DRAM_SDQS0_AE3") (pintype "bidirectional"))
    )
    (net (code "103") (name "/DDR3_DQS1_N") (class "Default")
      (node (ref "JP10M") (pin "27") (pinfunction "DQS1_N_27") (pintype "bidirectional"))
      (node (ref "U100") (pin "AE6") (pinfunction "DRAM_SDQS1_B_AE6") (pintype "bidirectional"))
    )
    (net (code "104") (name "/DDR3_DQS1_P") (class "Default")
      (node (ref "JP10M") (pin "29") (pinfunction "DQS1_P_29") (pintype "bidirectional"))
      (node (ref "U100") (pin "AD6") (pinfunction "DRAM_SDQS1_AD6") (pintype "bidirectional"))
    )
    (net (code "105") (name "/DDR3_DQS2_N") (class "Default")
      (node (ref "JP10M") (pin "45") (pinfunction "DQS2_N_45") (pintype "bidirectional"))
      (node (ref "U100") (pin "AE8") (pinfunction "DRAM_SDQS2_B_AE8") (pintype "bidirectional"))
    )
    (net (code "106") (name "/DDR3_DQS2_P") (class "Default")
      (node (ref "JP10M") (pin "47") (pinfunction "DQS2_P_47") (pintype "bidirectional"))
      (node (ref "U100") (pin "AD8") (pinfunction "DRAM_SDQS2_AD8") (pintype "bidirectional"))
    )
    (net (code "107") (name "/DDR3_DQS3_N") (class "Default")
      (node (ref "JP10M") (pin "62") (pinfunction "DQS3_N_62") (pintype "bidirectional"))
      (node (ref "U100") (pin "AB10") (pinfunction "DRAM_SDQS3_B_AB10") (pintype "bidirectional"))
    )
    (net (code "108") (name "/DDR3_DQS3_P") (class "Default")
      (node (ref "JP10M") (pin "64") (pinfunction "DQS3_P_64") (pintype "bidirectional"))
      (node (ref "U100") (pin "AC10") (pinfunction "DRAM_SDQS3_AC10") (pintype "bidirectional"))
    )
    (net (code "109") (name "/DDR3_DQS4_N") (class "Default")
      (node (ref "JP10M") (pin "135") (pinfunction "DQS4_N_135") (pintype "bidirectional"))
      (node (ref "U100") (pin "AE18") (pinfunction "DRAM_SDQS4_B_AE18") (pintype "bidirectional"))
    )
    (net (code "110") (name "/DDR3_DQS4_P") (class "Default")
      (node (ref "JP10M") (pin "137") (pinfunction "DQS4_P_137") (pintype "bidirectional"))
      (node (ref "U100") (pin "AD18") (pinfunction "DRAM_SDQS4_AD18") (pintype "bidirectional"))
    )
    (net (code "111") (name "/DDR3_DQS5_N") (class "Default")
      (node (ref "JP10M") (pin "152") (pinfunction "DQS5_N_152") (pintype "bidirectional"))
      (node (ref "U100") (pin "AE20") (pinfunction "DRAM_SDQS5_B_AE20") (pintype "bidirectional"))
    )
    (net (code "112") (name "/DDR3_DQS5_P") (class "Default")
      (node (ref "JP10M") (pin "154") (pinfunction "DQS5_P_154") (pintype "bidirectional"))
      (node (ref "U100") (pin "AD20") (pinfunction "DRAM_SDQS5_AD20") (pintype "bidirectional"))
    )
    (net (code "113") (name "/DDR3_DQS6_N") (class "Default")
      (node (ref "JP10M") (pin "169") (pinfunction "DQS6_N_169") (pintype "bidirectional"))
      (node (ref "U100") (pin "AE23") (pinfunction "DRAM_SDQS6_B_AE23") (pintype "bidirectional"))
    )
    (net (code "114") (name "/DDR3_DQS6_P") (class "Default")
      (node (ref "JP10M") (pin "171") (pinfunction "DQS6_P_171") (pintype "bidirectional"))
      (node (ref "U100") (pin "AD23") (pinfunction "DRAM_SDQS6_AD23") (pintype "bidirectional"))
    )
    (net (code "115") (name "/DDR3_DQS7_N") (class "Default")
      (node (ref "JP10M") (pin "186") (pinfunction "DQS7_N_186") (pintype "bidirectional"))
      (node (ref "U100") (pin "AA24") (pinfunction "DRAM_SDQS7_B_AA24") (pintype "bidirectional"))
    )
    (net (code "116") (name "/DDR3_DQS7_P") (class "Default")
      (node (ref "JP10M") (pin "188") (pinfunction "DQS7_P_188") (pintype "bidirectional"))
      (node (ref "U100") (pin "AA25") (pinfunction "DRAM_SDQS7_AA25") (pintype "bidirectional"))
    )
    (net (code "117") (name "/DDR3_EVENT_N") (class "Default")
      (node (ref "JP10M") (pin "198") (pinfunction "EVENT_N_198") (pintype "input"))
      (node (ref "R12M") (pin "2") (pinfunction "2_2") (pintype "passive"))
    )
    (net (code "118") (name "/DDR3_ODT0") (class "Default")
      (node (ref "JP10M") (pin "116") (pinfunction "ODT0_116") (pintype "input"))
      (node (ref "U100") (pin "AC16") (pinfunction "DRAM_SDODT0_AC16") (pintype "output"))
    )
    (net (code "119") (name "/DDR3_ODT1") (class "Default")
      (node (ref "JP10M") (pin "120") (pinfunction "ODT1_120") (pintype "input"))
      (node (ref "U100") (pin "AB17") (pinfunction "DRAM_SDODT1_AB17") (pintype "output"))
    )
    (net (code "120") (name "/DDR3_RAS") (class "Default")
      (node (ref "JP10M") (pin "110") (pinfunction "RAS_N_110") (pintype "input"))
      (node (ref "U100") (pin "AB15") (pinfunction "DRAM_RAS_AB15") (pintype "output"))
    )
    (net (code "121") (name "/DDR3_RESET") (class "Default")
      (node (ref "JP10M") (pin "30") (pinfunction "RESET_N_30") (pintype "input"))
      (node (ref "R10M") (pin "1") (pinfunction "1_1") (pintype "passive"))
      (node (ref "U100") (pin "Y6") (pinfunction "DRAM_RESET_Y6") (pintype "output"))
    )
    (net (code "122") (name "/DDR3_WE") (class "Default")
      (node (ref "JP10M") (pin "113") (pinfunction "WE_N_113") (pintype "input"))
      (node (ref "U100") (pin "AB16") (pinfunction "DRAM_SDWE_AB16") (pintype "output"))
    )
    (net (code "123") (name "/DDR3_ZQPAD") (class "Default")
      (node (ref "R11M") (pin "1") (pinfunction "1_1") (pintype "passive"))
      (node (ref "U100") (pin "AE17") (pinfunction "ZQPAD_AE17") (pintype "input"))
    )
    (net (code "124") (name "/SMB_SCL") (class "Default")
      (node (ref "JP10M") (pin "202") (pinfunction "SCL_202") (pintype "input"))
    )
    (net (code "125") (name "/SMB_SDA") (class "Default")
      (node (ref "JP10M") (pin "200") (pinfunction "SDA_200") (pintype "bidirectional"))
    )
    (net (code "126") (name "/VTT_VCNTL") (class "Default")
      (node (ref "C54M") (pin "1") (pinfunction "1_1") (pintype "passive"))
      (node (ref "R13M") (pin "2") (pinfunction "2_2") (pintype "passive"))
      (node (ref "U10M") (pin "6") (pinfunction "VCNTL_6") (pintype "passive"))
    )
    (net (code "127") (name "GND") (class "Default")
      (node (ref "C10M") (pin "2") (pinfunction "2_2") (pintype "passive"))
      (node (ref "C11M") (pin "2") (pinfunction "2_2") (pintype "passive"))
      (node (ref "C14M") (pin "2") (pinfunction "2_2") (pintype "passive"))
      (node (ref "C15M") (pin "2") (pinfunction "2_2") (pintype "passive"))
      (node (ref "C16M") (pin "2") (pinfunction "2_2") (pintype "passive"))
      (node (ref "C17M") (pin "2") (pinfunction "2_2") (pintype "passive"))
      (node (ref "C18M") (pin "2") (pinfunction "2_2") (pintype "passive"))
      (node (ref "C19M") (pin "2") (pinfunction "2_2") (pintype "passive"))
      (node (ref "C20M") (pin "2") (pinfunction "2_2") (pintype "passive"))
      (node (ref "C21M") (pin "2") (pinfunction "2_2") (pintype "passive"))
      (node (ref "C22M") (pin "2") (pinfunction "2_2") (pintype "passive"))
      (node (ref "C23M") (pin "2") (pinfunction "2_2") (pintype "passive"))
      (node (ref "C24M") (pin "2") (pinfunction "2_2") (pintype "passive"))
      (node (ref "C25M") (pin "2") (pinfunction "2_2") (pintype "passive"))
      (node (ref "C26M") (pin "2") (pinfunction "2_2") (pintype "passive"))
      (node (ref "C27M") (pin "2") (pinfunction "2_2") (pintype "passive"))
      (node (ref "C28M") (pin "2") (pinfunction "2_2") (pintype "passive"))
      (node (ref "C29M") (pin "2") (pinfunction "2_2") (pintype "passive"))
      (node (ref "C30M") (pin "2") (pinfunction "2_2") (pintype "passive"))
      (node (ref "C31M") (pin "2") (pinfunction "2_2") (pintype "passive"))
      (node (ref "C32M") (pin "2") (pinfunction "2_2") (pintype "passive"))
      (node (ref "C33M") (pin "2") (pinfunction "2_2") (pintype "passive"))
      (node (ref "C34M") (pin "2") (pinfunction "2_2") (pintype "passive"))
      (node (ref "C35M") (pin "2") (pinfunction "2_2") (pintype "passive"))
      (node (ref "C36M") (pin "2") (pinfunction "2_2") (pintype "passive"))
      (node (ref "C37M") (pin "2") (pinfunction "2_2") (pintype "passive"))
      (node (ref "C38M") (pin "2") (pinfunction "2_2") (pintype "passive"))
      (node (ref "C39M") (pin "2") (pinfunction "2_2") (pintype "passive"))
      (node (ref "C40M") (pin "2") (pinfunction "2_2") (pintype "passive"))
      (node (ref "C41M") (pin "2") (pinfunction "2_2") (pintype "passive"))
      (node (ref "C42M") (pin "2") (pinfunction "2_2") (pintype "passive"))
      (node (ref "C43M") (pin "2") (pinfunction "2_2") (pintype "passive"))
      (node (ref "C44M") (pin "2") (pinfunction "2_2") (pintype "passive"))
      (node (ref "C45M") (pin "2") (pinfunction "2_2") (pintype "passive"))
      (node (ref "C46M") (pin "2") (pinfunction "2_2") (pintype "passive"))
      (node (ref "C47M") (pin "2") (pinfunction "2_2") (pintype "passive"))
      (node (ref "C48M") (pin "2") (pinfunction "2_2") (pintype "passive"))
      (node (ref "C49M") (pin "2") (pinfunction "2_2") (pintype "passive"))
      (node (ref "C50M") (pin "2") (pinfunction "2_2") (pintype "passive"))
      (node (ref "C51M") (pin "2") (pinfunction "2_2") (pintype "passive"))
      (node (ref "C52M") (pin "2") (pinfunction "2_2") (pintype "passive"))
      (node (ref "C53M") (pin "2") (pinfunction "2_2") (pintype "passive"))
      (node (ref "C54M") (pin "2") (pinfunction "2_2") (pintype "passive"))
      (node (ref "C55M") (pin "2") (pinfunction "2_2") (pintype "passive"))
      (node (ref "C56M") (pin "2") (pinfunction "2_2") (pintype "passive"))
      (node (ref "JP10M") (pin "127") (pinfunction "VSS_127") (pintype "power_in"))
      (node (ref "JP10M") (pin "128") (pinfunction "VSS_128") (pintype "power_in"))
      (node (ref "JP10M") (pin "13") (pinfunction "VSS_13") (pintype "power_in"))
      (node (ref "JP10M") (pin "133") (pinfunction "VSS_133") (pintype "power_in"))
      (node (ref "JP10M") (pin "134") (pinfunction "VSS_134") (pintype "power_in"))
      (node (ref "JP10M") (pin "138") (pinfunction "VSS_138") (pintype "power_in"))
      (node (ref "JP10M") (pin "139") (pinfunction "VSS_139") (pintype "power_in"))
      (node (ref "JP10M") (pin "14") (pinfunction "VSS_14") (pintype "power_in"))
      (node (ref "JP10M") (pin "144") (pinfunction "VSS_144") (pintype "power_in"))
      (node (ref "JP10M") (pin "145") (pinfunction "VSS_145") (pintype "power_in"))
      (node (ref "JP10M") (pin "150") (pinfunction "VSS_150") (pintype "power_in"))
      (node (ref "JP10M") (pin "151") (pinfunction "VSS_151") (pintype "power_in"))
      (node (ref "JP10M") (pin "155") (pinfunction "VSS_155") (pintype "power_in"))
      (node (ref "JP10M") (pin "156") (pinfunction "VSS_156") (pintype "power_in"))
      (node (ref "JP10M") (pin "161") (pinfunction "VSS_161") (pintype "power_in"))
      (node (ref "JP10M") (pin "162") (pinfunction "VSS_162") (pintype "power_in"))
      (node (ref "JP10M") (pin "167") (pinfunction "VSS_167") (pintype "power_in"))
      (node (ref "JP10M") (pin "168") (pinfunction "VSS_168") (pintype "power_in"))
      (node (ref "JP10M") (pin "172") (pinfunction "VSS_172") (pintype "power_in"))
      (node (ref "JP10M") (pin "173") (pinfunction "VSS_173") (pintype "power_in"))
      (node (ref "JP10M") (pin "178") (pinfunction "VSS_178") (pintype "power_in"))
      (node (ref "JP10M") (pin "179") (pinfunction "VSS_179") (pintype "power_in"))
      (node (ref "JP10M") (pin "184") (pinfunction "VSS_184") (pintype "power_in"))
      (node (ref "JP10M") (pin "185") (pinfunction "VSS_185") (pintype "power_in"))
      (node (ref "JP10M") (pin "189") (pinfunction "VSS_189") (pintype "power_in"))
      (node (ref "JP10M") (pin "19") (pinfunction "VSS_19") (pintype "power_in"))
      (node (ref "JP10M") (pin "190") (pinfunction "VSS_190") (pintype "power_in"))
      (node (ref "JP10M") (pin "195") (pinfunction "VSS_195") (pintype "power_in"))
      (node (ref "JP10M") (pin "196") (pinfunction "VSS_196") (pintype "power_in"))
      (node (ref "JP10M") (pin "197") (pinfunction "SA0_197") (pintype "input"))
      (node (ref "JP10M") (pin "2") (pinfunction "VSS_2") (pintype "power_in"))
      (node (ref "JP10M") (pin "20") (pinfunction "VSS_20") (pintype "power_in"))
      (node (ref "JP10M") (pin "201") (pinfunction "SA1_201") (pintype "input"))
      (node (ref "JP10M") (pin "25") (pinfunction "VSS_25") (pintype "power_in"))
      (node (ref "JP10M") (pin "26") (pinfunction "VSS_26") (pintype "power_in"))
      (node (ref "JP10M") (pin "3") (pinfunction "VSS_3") (pintype "power_in"))
      (node (ref "JP10M") (pin "31") (pinfunction "VSS_31") (pintype "power_in"))
      (node (ref "JP10M") (pin "32") (pinfunction "VSS_32") (pintype "power_in"))
      (node (ref "JP10M") (pin "37") (pinfunction "VSS_37") (pintype "power_in"))
      (node (ref "JP10M") (pin "38") (pinfunction "VSS_38") (pintype "power_in"))
      (node (ref "JP10M") (pin "43") (pinfunction "VSS_43") (pintype "bidirectional"))
      (node (ref "JP10M") (pin "44") (pinfunction "VSS_44") (pintype "bidirectional"))
      (node (ref "JP10M") (pin "48") (pinfunction "VSS_48") (pintype "power_in"))
      (node (ref "JP10M") (pin "49") (pinfunction "VSS_49") (pintype "power_in"))
      (node (ref "JP10M") (pin "54") (pinfunction "VSS_54") (pintype "power_in"))
      (node (ref "JP10M") (pin "55") (pinfunction "VSS_55") (pintype "power_in"))
      (node (ref "JP10M") (pin "60") (pinfunction "VSS_60") (pintype "power_in"))
      (node (ref "JP10M") (pin "61") (pinfunction "VSS_61") (pintype "power_in"))
      (node (ref "JP10M") (pin "65") (pinfunction "VSS_65") (pintype "power_in"))
      (node (ref "JP10M") (pin "66") (pinfunction "VSS_66") (pintype "power_in"))
      (node (ref "JP10M") (pin "71") (pinfunction "VSS_71") (pintype "power_in"))
      (node (ref "JP10M") (pin "72") (pinfunction "VSS_72") (pintype "power_in"))
      (node (ref "JP10M") (pin "8") (pinfunction "VSS_8") (pintype "power_in"))
      (node (ref "JP10M") (pin "9") (pinfunction "VSS_9") (pintype "power_in"))
      (node (ref "R10M") (pin "2") (pinfunction "2_2") (pintype "passive"))
      (node (ref "R11M") (pin "2") (pinfunction "2_2") (pintype "passive"))
      (node (ref "R14M") (pin "2") (pinfunction "2_2") (pintype "passive"))
      (node (ref "U10M") (pin "2") (pinfunction "GND_2") (pintype "power_in"))
      (node (ref "U10M") (pin "9") (pinfunction "GND_9") (pintype "power_in"))
    )
    (net (code "128") (name "Net-(U10M-VIN)") (class "Default")
      (node (ref "C55M") (pin "1") (pinfunction "1_1") (pintype "passive"))
      (node (ref "R15M") (pin "2") (pinfunction "2_2") (pintype "passive"))
      (node (ref "R16M") (pin "2") (pinfunction "2_2") (pintype "passive"))
      (node (ref "U10M") (pin "1") (pinfunction "VIN_1") (pintype "power_in"))
    )
    (net (code "129") (name "P0.75V_DDR3_VTT") (class "Default")
      (node (ref "C18M") (pin "1") (pinfunction "1_1") (pintype "passive"))
      (node (ref "C19M") (pin "1") (pinfunction "1_1") (pintype "passive"))
      (node (ref "C20M") (pin "1") (pinfunction "1_1") (pintype "passive"))
      (node (ref "C56M") (pin "1") (pinfunction "1_1") (pintype "passive"))
      (node (ref "JP10M") (pin "203") (pinfunction "VTT_203") (pintype "power_in"))
      (node (ref "JP10M") (pin "204") (pinfunction "VTT_204") (pintype "power_in"))
      (node (ref "R14M") (pin "1") (pinfunction "1_1") (pintype "passive"))
      (node (ref "U10M") (pin "4") (pinfunction "VOUT_4") (pintype "power_in"))
    )
    (net (code "130") (name "P0.75V_REFDDR") (class "Default")
      (node (ref "C10M") (pin "1") (pinfunction "1_1") (pintype "passive"))
      (node (ref "C11M") (pin "1") (pinfunction "1_1") (pintype "passive"))
      (node (ref "C14M") (pin "1") (pinfunction "1_1") (pintype "passive"))
      (node (ref "C15M") (pin "1") (pinfunction "1_1") (pintype "passive"))
      (node (ref "C16M") (pin "1") (pinfunction "1_1") (pintype "passive"))
      (node (ref "C40M") (pin "1") (pinfunction "1_1") (pintype "passive"))
      (node (ref "JP10M") (pin "1") (pinfunction "VREFDQ_1") (pintype "power_in"))
      (node (ref "JP10M") (pin "126") (pinfunction "VREFCA_126") (pintype "power_in"))
      (node (ref "U100") (pin "AC2") (pinfunction "DRAM_VREF_AC2") (pintype "power_in"))
      (node (ref "U10M") (pin "3") (pinfunction "REFEN_3") (pintype "passive"))
    )
    (net (code "131") (name "P1.5V_DDR_SW3") (class "Default")
      (node (ref "C21M") (pin "1") (pinfunction "1_1") (pintype "passive"))
      (node (ref "C22M") (pin "1") (pinfunction "1_1") (pintype "passive"))
      (node (ref "C23M") (pin "1") (pinfunction "1_1") (pintype "passive"))
      (node (ref "C24M") (pin "1") (pinfunction "1_1") (pintype "passive"))
      (node (ref "C25M") (pin "1") (pinfunction "1_1") (pintype "passive"))
      (node (ref "C26M") (pin "1") (pinfunction "1_1") (pintype "passive"))
      (node (ref "C27M") (pin "1") (pinfunction "1_1") (pintype "passive"))
      (node (ref "C28M") (pin "1") (pinfunction "1_1") (pintype "passive"))
      (node (ref "C29M") (pin "1") (pinfunction "1_1") (pintype "passive"))
      (node (ref "C30M") (pin "1") (pinfunction "1_1") (pintype "passive"))
      (node (ref "C31M") (pin "1") (pinfunction "1_1") (pintype "passive"))
      (node (ref "C32M") (pin "1") (pinfunction "1_1") (pintype "passive"))
      (node (ref "C33M") (pin "1") (pinfunction "1_1") (pintype "passive"))
      (node (ref "C34M") (pin "1") (pinfunction "1_1") (pintype "passive"))
      (node (ref "C35M") (pin "1") (pinfunction "1_1") (pintype "passive"))
      (node (ref "C36M") (pin "1") (pinfunction "1_1") (pintype "passive"))
      (node (ref "C37M") (pin "1") (pinfunction "1_1") (pintype "passive"))
      (node (ref "C38M") (pin "1") (pinfunction "1_1") (pintype "passive"))
      (node (ref "C39M") (pin "1") (pinfunction "1_1") (pintype "passive"))
      (node (ref "C41M") (pin "1") (pinfunction "1_1") (pintype "passive"))
      (node (ref "C42M") (pin "1") (pinfunction "1_1") (pintype "passive"))
      (node (ref "C43M") (pin "1") (pinfunction "1_1") (pintype "passive"))
      (node (ref "C44M") (pin "1") (pinfunction "1_1") (pintype "passive"))
      (node (ref "C45M") (pin "1") (pinfunction "1_1") (pintype "passive"))
      (node (ref "C46M") (pin "1") (pinfunction "1_1") (pintype "passive"))
      (node (ref "C47M") (pin "1") (pinfunction "1_1") (pintype "passive"))
      (node (ref "C48M") (pin "1") (pinfunction "1_1") (pintype "passive"))
      (node (ref "C49M") (pin "1") (pinfunction "1_1") (pintype "passive"))
      (node (ref "C50M") (pin "1") (pinfunction "1_1") (pintype "passive"))
      (node (ref "C51M") (pin "1") (pinfunction "1_1") (pintype "passive"))
      (node (ref "C52M") (pin "1") (pinfunction "1_1") (pintype "passive"))
      (node (ref "C53M") (pin "1") (pinfunction "1_1") (pintype "passive"))
      (node (ref "JP10M") (pin "100") (pinfunction "VDD_100") (pintype "power_in"))
      (node (ref "JP10M") (pin "105") (pinfunction "VDD_105") (pintype "power_in"))
      (node (ref "JP10M") (pin "106") (pinfunction "VDD_106") (pintype "power_in"))
      (node (ref "JP10M") (pin "111") (pinfunction "VDD_111") (pintype "power_in"))
      (node (ref "JP10M") (pin "112") (pinfunction "VDD_112") (pintype "power_in"))
      (node (ref "JP10M") (pin "117") (pinfunction "VDD_117") (pintype "power_in"))
      (node (ref "JP10M") (pin "118") (pinfunction "VDD_118") (pintype "power_in"))
      (node (ref "JP10M") (pin "123") (pinfunction "VDD_123") (pintype "power_in"))
      (node (ref "JP10M") (pin "124") (pinfunction "VDD_124") (pintype "power_in"))
      (node (ref "JP10M") (pin "75") (pinfunction "VDD_75") (pintype "power_in"))
      (node (ref "JP10M") (pin "76") (pinfunction "VDD_76") (pintype "power_in"))
      (node (ref "JP10M") (pin "81") (pinfunction "VDD_81") (pintype "power_in"))
      (node (ref "JP10M") (pin "82") (pinfunction "VDD_82") (pintype "power_in"))
      (node (ref "JP10M") (pin "87") (pinfunction "VDD_87") (pintype "power_in"))
      (node (ref "JP10M") (pin "88") (pinfunction "VDD_88") (pintype "power_in"))
      (node (ref "JP10M") (pin "93") (pinfunction "VDD_93") (pintype "power_in"))
      (node (ref "JP10M") (pin "94") (pinfunction "VDD_94") (pintype "power_in"))
      (node (ref "JP10M") (pin "99") (pinfunction "VDD_99") (pintype "power_in"))
      (node (ref "R15M") (pin "1") (pinfunction "1_1") (pintype "passive"))
      (node (ref "U100") (pin "R18") (pinfunction "NVCC_DRAM_1_R18") (pintype "power_in"))
      (node (ref "U100") (pin "T18") (pinfunction "NVCC_DRAM_2_T18") (pintype "power_in"))
      (node (ref "U100") (pin "U18") (pinfunction "NVCC_DRAM_3_U18") (pintype "power_in"))
      (node (ref "U100") (pin "V10") (pinfunction "NVCC_DRAM_4_V10") (pintype "power_in"))
      (node (ref "U100") (pin "V11") (pinfunction "NVCC_DRAM_5_V11") (pintype "power_in"))
      (node (ref "U100") (pin "V12") (pinfunction "NVCC_DRAM_6_V12") (pintype "power_in"))
      (node (ref "U100") (pin "V13") (pinfunction "NVCC_DRAM_7_V13") (pintype "power_in"))
      (node (ref "U100") (pin "V14") (pinfunction "NVCC_DRAM_8_V14") (pintype "power_in"))
      (node (ref "U100") (pin "V15") (pinfunction "NVCC_DRAM_9_V15") (pintype "power_in"))
      (node (ref "U100") (pin "V16") (pinfunction "NVCC_DRAM_10_V16") (pintype "power_in"))
      (node (ref "U100") (pin "V17") (pinfunction "NVCC_DRAM_11_V17") (pintype "power_in"))
      (node (ref "U100") (pin "V18") (pinfunction "NVCC_DRAM_12_V18") (pintype "power_in"))
      (node (ref "U100") (pin "V9") (pinfunction "NVCC_DRAM_13_V9") (pintype "power_in"))
    )
    (net (code "132") (name "P1.8V_SW4") (class "Default")
      (node (ref "R16M") (pin "1") (pinfunction "1_1") (pintype "passive"))
    )
    (net (code "133") (name "P3.3V_DELAYED") (class "Default")
      (node (ref "C17M") (pin "1") (pinfunction "1_1") (pintype "passive"))
      (node (ref "JP10M") (pin "199") (pinfunction "VDDSPD_199") (pintype "power_in"))
      (node (ref "R12M") (pin "1") (pinfunction "1_1") (pintype "passive"))
    )
    (net (code "134") (name "P5.0V") (class "Default")
      (node (ref "R13M") (pin "1") (pinfunction "1_1") (pintype "passive"))
    )
  )
)
